# IR_Sensor.net
KiCad netlist of a schematic drawn in EAGLE
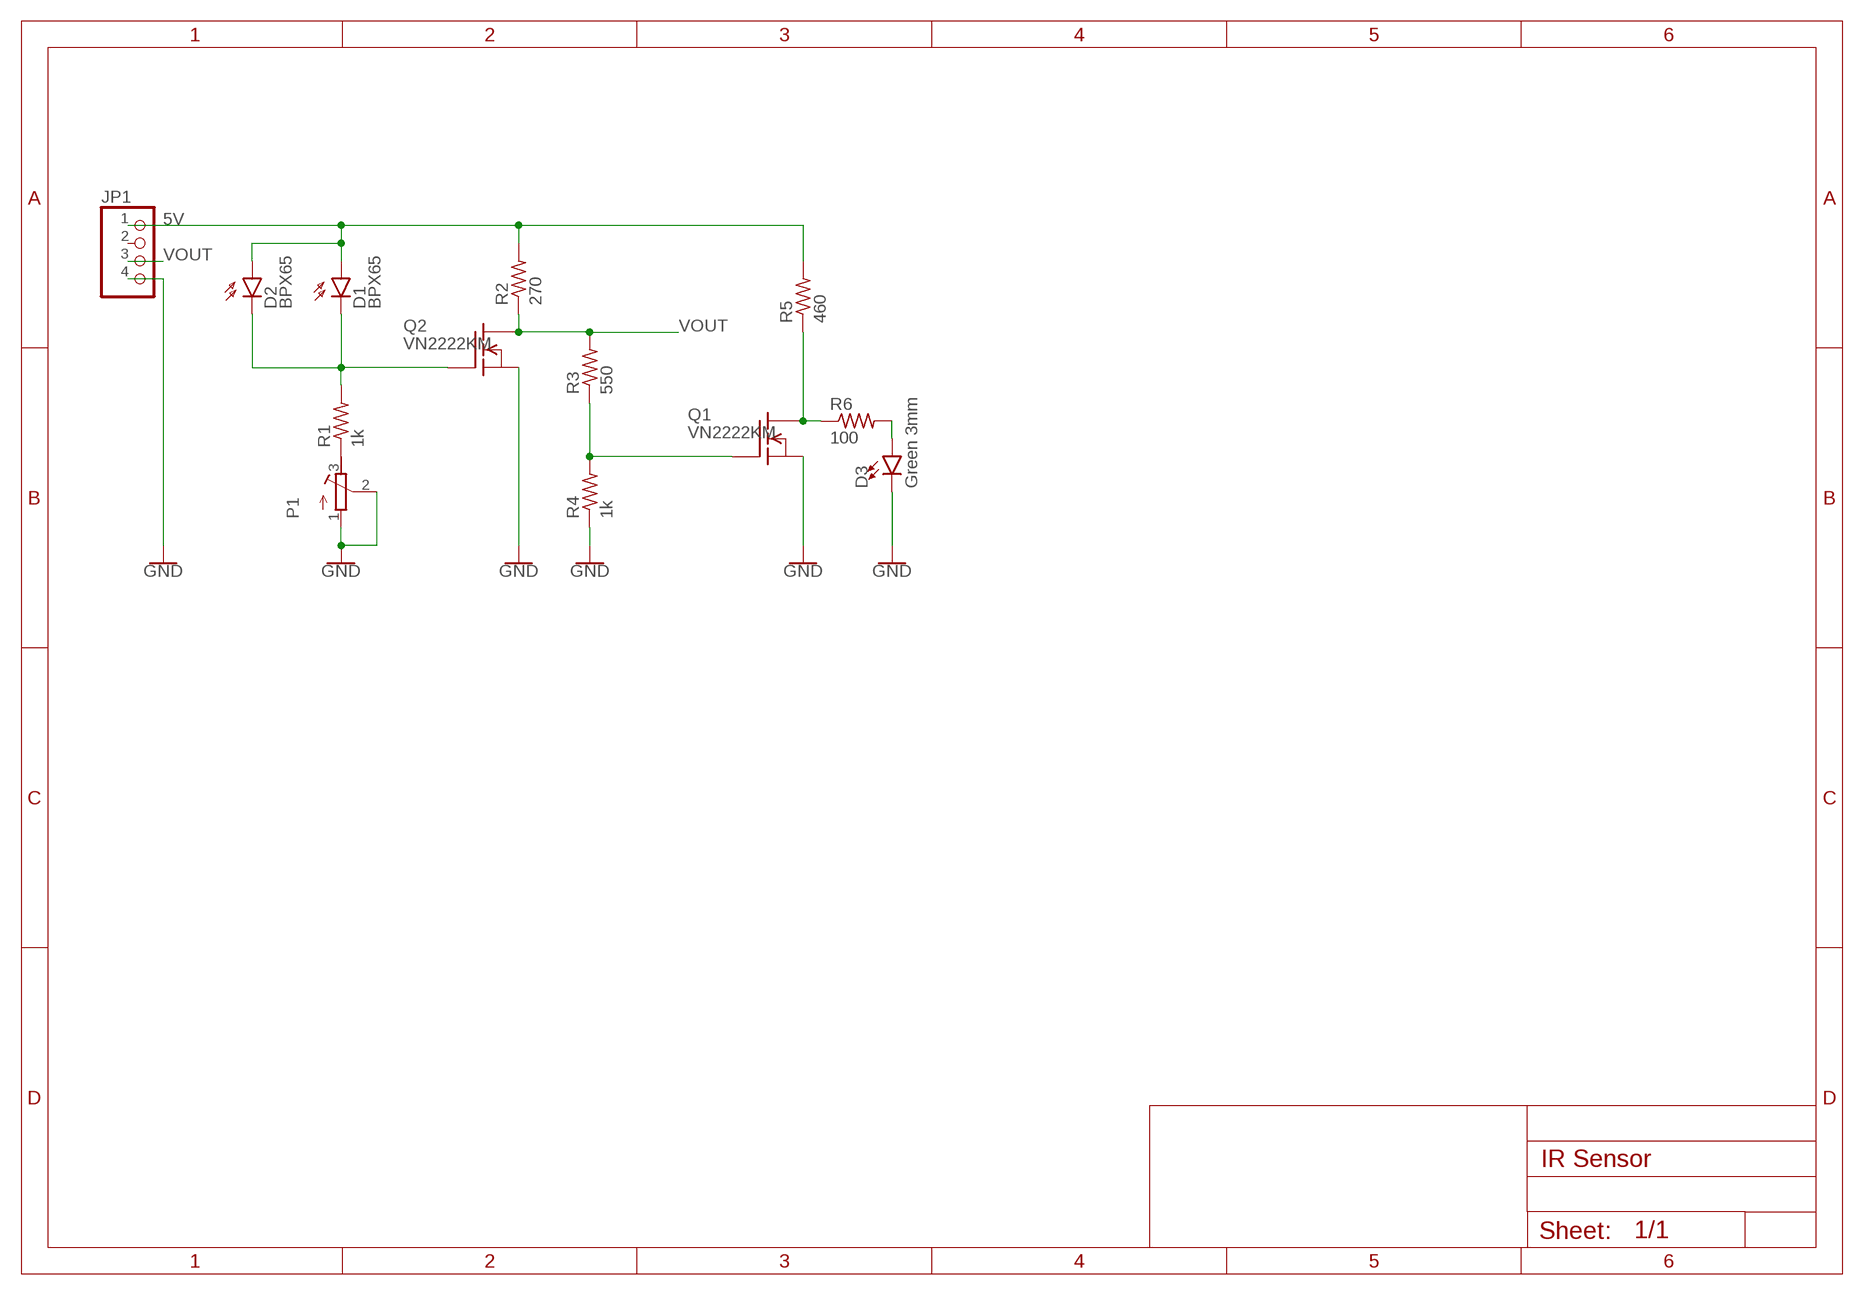
[diagram p0: schematic, sheet 1]

(export (version "E")
  (design (tool "Eeschema 10.0.6"))
  (components
    (comp (ref "D1")
      (value "BPX65")
      (footprint "eagle-import:BPX65")
      (fields (field (name "MPN") "BPX65."))
      (libsource (lib "eagle-import") (part "BPX65"))
    )
    (comp (ref "D2")
      (value "BPX65")
      (footprint "eagle-import:BPX65")
      (fields (field (name "MPN") "BPX65."))
      (libsource (lib "eagle-import") (part "BPX65"))
    )
    (comp (ref "D3")
      (value "Green 3mm")
      (footprint "eagle-import:LED_3MM")
      (libsource (lib "eagle-import") (part "LED3MM"))
    )
    (comp (ref "JP1")
      (value "PINHD-1X4")
      (footprint "eagle-import:1X04")
      (libsource (lib "eagle-import") (part "PINHD-1X4"))
    )
    (comp (ref "P1")
      (value "R-TRIMM64W")
      (footprint "eagle-import:RTRIM64W")
      (libsource (lib "eagle-import") (part "R-TRIMM64W"))
    )
    (comp (ref "Q1")
      (value "VN2222KM")
      (footprint "eagle-import:TO237")
      (libsource (lib "eagle-import") (part "VN2222KM"))
    )
    (comp (ref "Q2")
      (value "VN2222KM")
      (footprint "eagle-import:TO237")
      (libsource (lib "eagle-import") (part "VN2222KM"))
    )
    (comp (ref "R1")
      (value "1k")
      (footprint "eagle-import:0204_7")
      (libsource (lib "eagle-import") (part "R-US_0204/7"))
    )
    (comp (ref "R2")
      (value "270")
      (footprint "eagle-import:0204_7")
      (libsource (lib "eagle-import") (part "R-US_0204/7"))
    )
    (comp (ref "R3")
      (value "550")
      (footprint "eagle-import:0204_7")
      (libsource (lib "eagle-import") (part "R-US_0204/7"))
    )
    (comp (ref "R4")
      (value "1k")
      (footprint "eagle-import:0204_7")
      (libsource (lib "eagle-import") (part "R-US_0204/7"))
    )
    (comp (ref "R5")
      (value "460")
      (footprint "eagle-import:0204_7")
      (libsource (lib "eagle-import") (part "R-US_0204/7"))
    )
    (comp (ref "R6")
      (value "100")
      (footprint "eagle-import:0204_7")
      (libsource (lib "eagle-import") (part "R-US_0204/7"))
    )
  )
  (nets
    (net (code "1") (name "/5V") (class "Default")
      (node (ref "D1") (pin "A") (pinfunction "A_A") (pintype "passive"))
      (node (ref "D2") (pin "A") (pinfunction "A_A") (pintype "passive"))
      (node (ref "JP1") (pin "1") (pinfunction "1_1") (pintype "passive"))
      (node (ref "R2") (pin "2") (pinfunction "2_2") (pintype "passive"))
      (node (ref "R5") (pin "2") (pinfunction "2_2") (pintype "passive"))
    )
    (net (code "2") (name "/VOUT") (class "Default")
      (node (ref "JP1") (pin "3") (pinfunction "3_3") (pintype "passive"))
      (node (ref "Q2") (pin "1") (pinfunction "D_1") (pintype "passive"))
      (node (ref "R2") (pin "1") (pinfunction "1_1") (pintype "passive"))
      (node (ref "R3") (pin "2") (pinfunction "2_2") (pintype "passive"))
    )
    (net (code "3") (name "GND") (class "Default")
      (node (ref "D3") (pin "K") (pinfunction "C_K") (pintype "passive"))
      (node (ref "JP1") (pin "4") (pinfunction "4_4") (pintype "passive"))
      (node (ref "P1") (pin "1") (pinfunction "A_1") (pintype "passive"))
      (node (ref "P1") (pin "2") (pinfunction "S_2") (pintype "passive"))
      (node (ref "Q1") (pin "3") (pinfunction "S_3") (pintype "passive"))
      (node (ref "Q2") (pin "3") (pinfunction "S_3") (pintype "passive"))
      (node (ref "R4") (pin "1") (pinfunction "1_1") (pintype "passive"))
    )
    (net (code "4") (name "Net-(D1-C)") (class "Default")
      (node (ref "D1") (pin "K") (pinfunction "C_K") (pintype "passive"))
      (node (ref "D2") (pin "K") (pinfunction "C_K") (pintype "passive"))
      (node (ref "Q2") (pin "2") (pinfunction "G_2") (pintype "passive"))
      (node (ref "R1") (pin "2") (pinfunction "2_2") (pintype "passive"))
    )
    (net (code "5") (name "Net-(D3-PadA)") (class "Default")
      (node (ref "D3") (pin "A") (pinfunction "A_A") (pintype "passive"))
      (node (ref "R6") (pin "2") (pinfunction "2_2") (pintype "passive"))
    )
    (net (code "6") (name "Net-(P1-E)") (class "Default")
      (node (ref "P1") (pin "3") (pinfunction "E_3") (pintype "passive"))
      (node (ref "R1") (pin "1") (pinfunction "1_1") (pintype "passive"))
    )
    (net (code "7") (name "Net-(Q1-D)") (class "Default")
      (node (ref "Q1") (pin "1") (pinfunction "D_1") (pintype "passive"))
      (node (ref "R5") (pin "1") (pinfunction "1_1") (pintype "passive"))
      (node (ref "R6") (pin "1") (pinfunction "1_1") (pintype "passive"))
    )
    (net (code "8") (name "Net-(Q1-G)") (class "Default")
      (node (ref "Q1") (pin "2") (pinfunction "G_2") (pintype "passive"))
      (node (ref "R3") (pin "1") (pinfunction "1_1") (pintype "passive"))
      (node (ref "R4") (pin "2") (pinfunction "2_2") (pintype "passive"))
    )
    (net (code "9") (name "unconnected-(JP1-Pad2)") (class "Default")
      (node (ref "JP1") (pin "2") (pinfunction "2_2") (pintype "passive"))
    )
  )
)
